# Demo1.net
KiCad netlist of a schematic drawn in Altium Designer
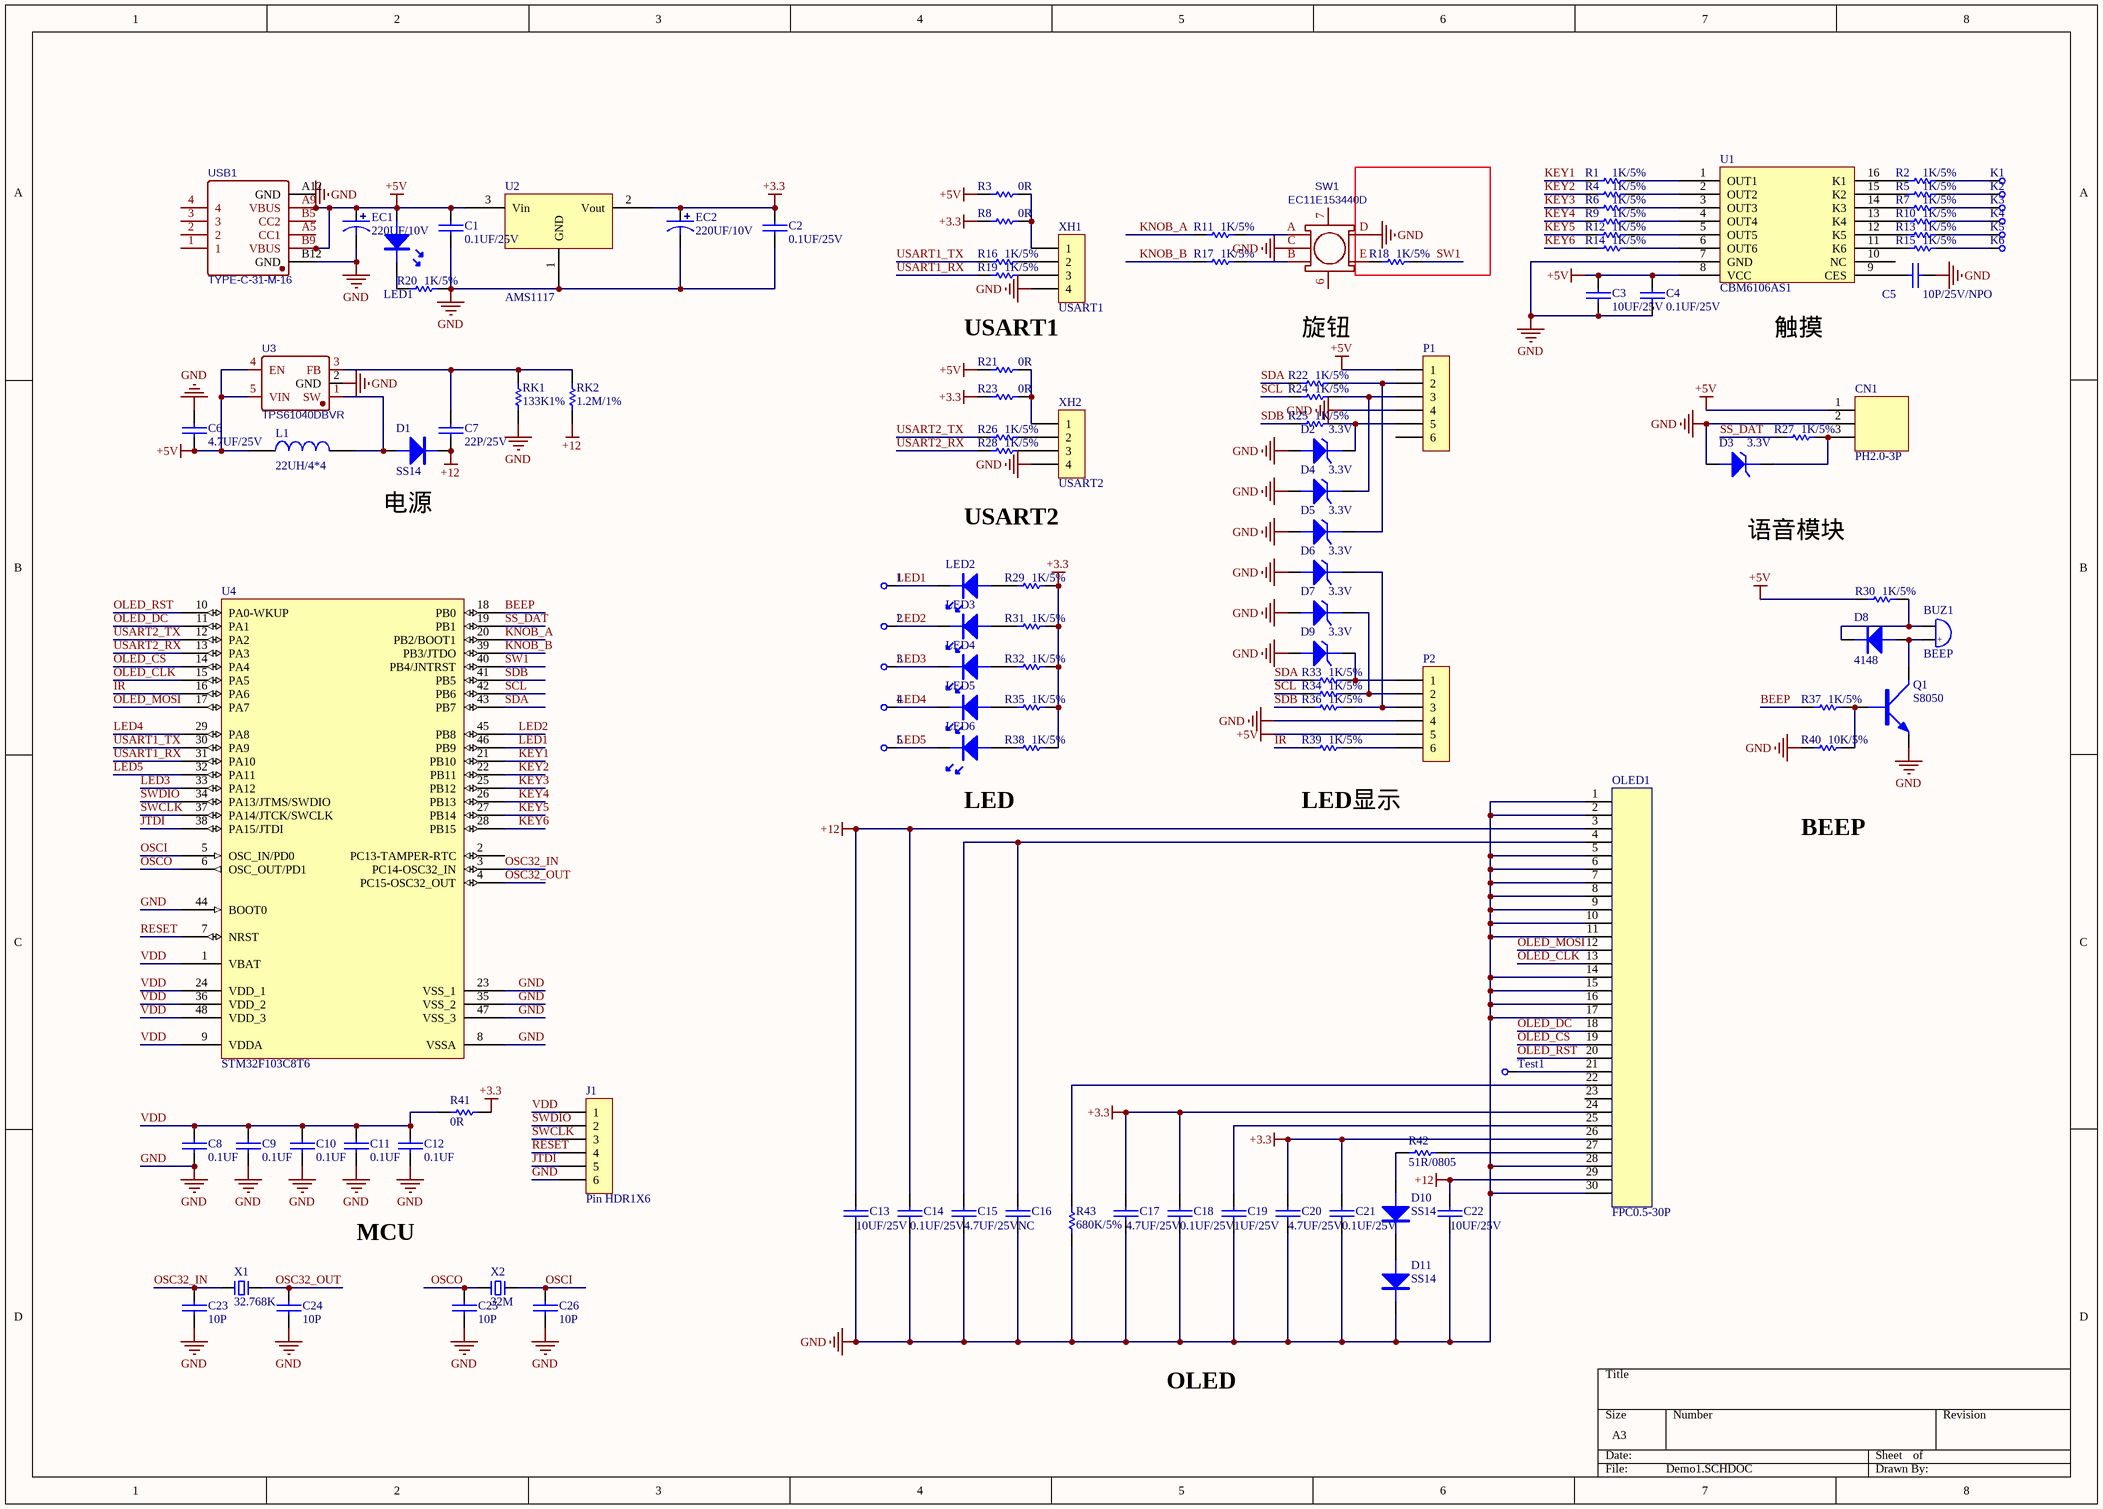
[diagram p0: Demo1.SCHDOC]

(export (version "E")
  (design (tool "Eeschema 10.0.6"))
  (components
    (comp (ref "1")
      (value "CHECK")
      (footprint "CHECK-A")
      (description "测试点")
      (libsource (lib "Fszhang") (part "CHECK"))
    )
    (comp (ref "2")
      (value "CHECK")
      (footprint "CHECK-A")
      (description "测试点")
      (libsource (lib "Fszhang") (part "CHECK"))
    )
    (comp (ref "3")
      (value "CHECK")
      (footprint "CHECK-A")
      (description "测试点")
      (libsource (lib "Fszhang") (part "CHECK"))
    )
    (comp (ref "4")
      (value "CHECK")
      (footprint "CHECK-A")
      (description "测试点")
      (libsource (lib "Fszhang") (part "CHECK"))
    )
    (comp (ref "5")
      (value "CHECK")
      (footprint "CHECK-A")
      (description "测试点")
      (libsource (lib "Fszhang") (part "CHECK"))
    )
    (comp (ref "BUZ1")
      (value "BEEP")
      (footprint "BEEP 6.5x12x6")
      (description "蜂鸣器")
      (libsource (lib "蜂鸣器") (part "BEEP"))
    )
    (comp (ref "C1")
      (value "0.1UF/25V")
      (footprint "0603C")
      (description "无极性电容")
      (libsource (lib "电容") (part "CAP"))
    )
    (comp (ref "C2")
      (value "0.1UF/25V")
      (footprint "0603C")
      (description "无极性电容")
      (libsource (lib "电容") (part "CAP"))
    )
    (comp (ref "C3")
      (value "10UF/25V")
      (footprint "0603C")
      (description "无极性电容")
      (libsource (lib "电容") (part "CAP"))
    )
    (comp (ref "C4")
      (value "0.1UF/25V")
      (footprint "0603C")
      (description "无极性电容")
      (libsource (lib "电容") (part "CAP"))
    )
    (comp (ref "C5")
      (value "10P/25V/NPO")
      (footprint "0603C")
      (description "无极性电容")
      (libsource (lib "电容") (part "CAP"))
    )
    (comp (ref "C6")
      (value "4.7UF/25V")
      (footprint "0603C")
      (description "无极性电容")
      (libsource (lib "电容") (part "CAP"))
    )
    (comp (ref "C7")
      (value "22P/25V")
      (footprint "0603C")
      (description "无极性电容")
      (libsource (lib "电容") (part "CAP"))
    )
    (comp (ref "C8")
      (value "0.1UF")
      (footprint "0603C")
      (description "无极性电容")
      (libsource (lib "电容") (part "CAP"))
    )
    (comp (ref "C9")
      (value "0.1UF")
      (footprint "0603C")
      (description "无极性电容")
      (libsource (lib "电容") (part "CAP"))
    )
    (comp (ref "C10")
      (value "0.1UF")
      (footprint "0603C")
      (description "无极性电容")
      (libsource (lib "电容") (part "CAP"))
    )
    (comp (ref "C11")
      (value "0.1UF")
      (footprint "0603C")
      (description "无极性电容")
      (libsource (lib "电容") (part "CAP"))
    )
    (comp (ref "C12")
      (value "0.1UF")
      (footprint "0603C")
      (description "无极性电容")
      (libsource (lib "电容") (part "CAP"))
    )
    (comp (ref "C13")
      (value "10UF/25V")
      (footprint "0603C")
      (description "无极性电容")
      (libsource (lib "电容") (part "CAP"))
    )
    (comp (ref "C14")
      (value "0.1UF/25V")
      (footprint "0603C")
      (description "无极性电容")
      (libsource (lib "电容") (part "CAP"))
    )
    (comp (ref "C15")
      (value "4.7UF/25V")
      (footprint "0603C")
      (description "无极性电容")
      (libsource (lib "电容") (part "CAP"))
    )
    (comp (ref "C16")
      (value "NC")
      (footprint "0603C")
      (description "无极性电容")
      (libsource (lib "电容") (part "CAP"))
    )
    (comp (ref "C17")
      (value "4.7UF/25V")
      (footprint "0603C")
      (description "无极性电容")
      (libsource (lib "电容") (part "CAP"))
    )
    (comp (ref "C18")
      (value "0.1UF/25V")
      (footprint "0603C")
      (description "无极性电容")
      (libsource (lib "电容") (part "CAP"))
    )
    (comp (ref "C19")
      (value "1UF/25V")
      (footprint "0603C")
      (description "无极性电容")
      (libsource (lib "电容") (part "CAP"))
    )
    (comp (ref "C20")
      (value "4.7UF/25V")
      (footprint "0603C")
      (description "无极性电容")
      (libsource (lib "电容") (part "CAP"))
    )
    (comp (ref "C21")
      (value "0.1UF/25V")
      (footprint "0603C")
      (description "无极性电容")
      (libsource (lib "电容") (part "CAP"))
    )
    (comp (ref "C22")
      (value "10UF/25V")
      (footprint "0603C")
      (description "无极性电容")
      (libsource (lib "电容") (part "CAP"))
    )
    (comp (ref "C23")
      (value "10P")
      (footprint "0603C")
      (description "无极性电容")
      (libsource (lib "电容") (part "CAP"))
    )
    (comp (ref "C24")
      (value "10P")
      (footprint "0603C")
      (description "无极性电容")
      (libsource (lib "电容") (part "CAP"))
    )
    (comp (ref "C25")
      (value "10P")
      (footprint "0603C")
      (description "无极性电容")
      (libsource (lib "电容") (part "CAP"))
    )
    (comp (ref "C26")
      (value "10P")
      (footprint "0603C")
      (description "无极性电容")
      (libsource (lib "电容") (part "CAP"))
    )
    (comp (ref "CN1") (value "PH2.0-3P") (footprint "PH2.0-3P") (libsource (lib "PH") (part "PH2.0-3P")))
    (comp (ref "D1")
      (value "SS14")
      (footprint "SMA/DO-214AC")
      (description "普通二极管")
      (libsource (lib "二极管") (part "DIODE"))
    )
    (comp (ref "D2")
      (value "3.3V")
      (footprint "SOD-123")
      (description "稳压二极管")
      (libsource (lib "二极管") (part "DIODE ZENER"))
    )
    (comp (ref "D3")
      (value "3.3V")
      (footprint "SOD-123")
      (description "稳压二极管")
      (libsource (lib "二极管") (part "DIODE ZENER"))
    )
    (comp (ref "D4")
      (value "3.3V")
      (footprint "SOD-123")
      (description "稳压二极管")
      (libsource (lib "二极管") (part "DIODE ZENER"))
    )
    (comp (ref "D5")
      (value "3.3V")
      (footprint "SOD-123")
      (description "稳压二极管")
      (libsource (lib "二极管") (part "DIODE ZENER"))
    )
    (comp (ref "D6")
      (value "3.3V")
      (footprint "SOD-123")
      (description "稳压二极管")
      (libsource (lib "二极管") (part "DIODE ZENER"))
    )
    (comp (ref "D7")
      (value "3.3V")
      (footprint "SOD-123")
      (description "稳压二极管")
      (libsource (lib "二极管") (part "DIODE ZENER"))
    )
    (comp (ref "D8")
      (value "4148")
      (footprint "SOD-123")
      (description "普通二极管")
      (libsource (lib "二极管") (part "DIODE"))
    )
    (comp (ref "D9")
      (value "3.3V")
      (footprint "SOD-123")
      (description "稳压二极管")
      (libsource (lib "二极管") (part "DIODE ZENER"))
    )
    (comp (ref "D10")
      (value "SS14")
      (footprint "SMA/DO-214AC")
      (description "普通二极管")
      (libsource (lib "二极管") (part "DIODE"))
    )
    (comp (ref "D11")
      (value "SS14")
      (footprint "SMA/DO-214AC")
      (description "普通二极管")
      (libsource (lib "二极管") (part "DIODE"))
    )
    (comp (ref "EC1")
      (value "220UF/10V")
      (footprint "SMD-EC6.3X6.3X10")
      (description "贴片电解电容")
      (libsource (lib "电容") (part "SMD_ECAP"))
    )
    (comp (ref "EC2")
      (value "220UF/10V")
      (footprint "SMD-EC6.3X6.3X10")
      (description "贴片电解电容")
      (libsource (lib "电容") (part "SMD_ECAP"))
    )
    (comp (ref "J1")
      (value "Pin HDR1X6")
      (footprint "Pin HDR1X6/2.54mm-S")
      (libsource (lib "排针") (part "Pin HDR1X6"))
    )
    (comp (ref "K1")
      (value "CHECK")
      (footprint "CHECK-A")
      (description "测试点")
      (libsource (lib "Fszhang") (part "CHECK"))
    )
    (comp (ref "K2")
      (value "CHECK")
      (footprint "CHECK-A")
      (description "测试点")
      (libsource (lib "Fszhang") (part "CHECK"))
    )
    (comp (ref "K3")
      (value "CHECK")
      (footprint "CHECK-A")
      (description "测试点")
      (libsource (lib "Fszhang") (part "CHECK"))
    )
    (comp (ref "K4")
      (value "CHECK")
      (footprint "CHECK-A")
      (description "测试点")
      (libsource (lib "Fszhang") (part "CHECK"))
    )
    (comp (ref "K5")
      (value "CHECK")
      (footprint "CHECK-A")
      (description "测试点")
      (libsource (lib "Fszhang") (part "CHECK"))
    )
    (comp (ref "K6")
      (value "CHECK")
      (footprint "CHECK-A")
      (description "测试点")
      (libsource (lib "Fszhang") (part "CHECK"))
    )
    (comp (ref "L1")
      (value "22UH/4*4")
      (footprint "CD42")
      (description "INDUCTOR")
      (libsource (lib "电感") (part "INDUCTOR"))
    )
    (comp (ref "LED1") (value "~") (footprint "LED-0603W") (libsource (lib "LED") (part "LED")))
    (comp (ref "LED2") (value "~") (footprint "LED-0603W") (libsource (lib "LED") (part "LED")))
    (comp (ref "LED3") (value "~") (footprint "LED-0603W") (libsource (lib "LED") (part "LED")))
    (comp (ref "LED4") (value "~") (footprint "LED-0603W") (libsource (lib "LED") (part "LED")))
    (comp (ref "LED5") (value "~") (footprint "LED-0603W") (libsource (lib "LED") (part "LED")))
    (comp (ref "LED6") (value "~") (footprint "LED-0603W") (libsource (lib "LED") (part "LED")))
    (comp (ref "OLED1")
      (value "FPC0.5-30P")
      (footprint "FPC0.5-30P")
      (description "贴片")
      (libsource (lib "FPC") (part "FPC0.5-30P"))
    )
    (comp (ref "P1") (value "~") (footprint "Pin HDR1X6/2.54mm-S") (libsource (lib "排针") (part "Pin HDR1X6")))
    (comp (ref "P2") (value "~") (footprint "Pin HDR1X6/2.54mm-S") (libsource (lib "排针") (part "Pin HDR1X6")))
    (comp (ref "Q1")
      (value "S8050")
      (footprint "SOT-23")
      (description "NPN三极管")
      (libsource (lib "三极管") (part "NPN"))
    )
    (comp (ref "R1") (value "1K/5%") (footprint "0603R") (libsource (lib "电阻") (part "RES")))
    (comp (ref "R2") (value "1K/5%") (footprint "0603R") (libsource (lib "电阻") (part "RES")))
    (comp (ref "R3") (value "0R") (footprint "0603R") (libsource (lib "电阻") (part "RES")))
    (comp (ref "R4") (value "1K/5%") (footprint "0603R") (libsource (lib "电阻") (part "RES")))
    (comp (ref "R5") (value "1K/5%") (footprint "0603R") (libsource (lib "电阻") (part "RES")))
    (comp (ref "R6") (value "1K/5%") (footprint "0603R") (libsource (lib "电阻") (part "RES")))
    (comp (ref "R7") (value "1K/5%") (footprint "0603R") (libsource (lib "电阻") (part "RES")))
    (comp (ref "R8") (value "0R") (footprint "0603R") (libsource (lib "电阻") (part "RES")))
    (comp (ref "R9") (value "1K/5%") (footprint "0603R") (libsource (lib "电阻") (part "RES")))
    (comp (ref "R10") (value "1K/5%") (footprint "0603R") (libsource (lib "电阻") (part "RES")))
    (comp (ref "R11") (value "1K/5%") (footprint "0603R") (libsource (lib "电阻") (part "RES")))
    (comp (ref "R12") (value "1K/5%") (footprint "0603R") (libsource (lib "电阻") (part "RES")))
    (comp (ref "R13") (value "1K/5%") (footprint "0603R") (libsource (lib "电阻") (part "RES")))
    (comp (ref "R14") (value "1K/5%") (footprint "0603R") (libsource (lib "电阻") (part "RES")))
    (comp (ref "R15") (value "1K/5%") (footprint "0603R") (libsource (lib "电阻") (part "RES")))
    (comp (ref "R16") (value "1K/5%") (footprint "0603R") (libsource (lib "电阻") (part "RES")))
    (comp (ref "R17") (value "1K/5%") (footprint "0603R") (libsource (lib "电阻") (part "RES")))
    (comp (ref "R18") (value "1K/5%") (footprint "0603R") (libsource (lib "电阻") (part "RES")))
    (comp (ref "R19") (value "1K/5%") (footprint "0603R") (libsource (lib "电阻") (part "RES")))
    (comp (ref "R20") (value "1K/5%") (footprint "0603R") (libsource (lib "电阻") (part "RES")))
    (comp (ref "R21") (value "0R") (footprint "0603R") (libsource (lib "电阻") (part "RES")))
    (comp (ref "R22") (value "1K/5%") (footprint "0603R") (libsource (lib "电阻") (part "RES")))
    (comp (ref "R23") (value "0R") (footprint "0603R") (libsource (lib "电阻") (part "RES")))
    (comp (ref "R24") (value "1K/5%") (footprint "0603R") (libsource (lib "电阻") (part "RES")))
    (comp (ref "R25") (value "1K/5%") (footprint "0603R") (libsource (lib "电阻") (part "RES")))
    (comp (ref "R26") (value "1K/5%") (footprint "0603R") (libsource (lib "电阻") (part "RES")))
    (comp (ref "R27") (value "1K/5%") (footprint "0603R") (libsource (lib "电阻") (part "RES")))
    (comp (ref "R28") (value "1K/5%") (footprint "0603R") (libsource (lib "电阻") (part "RES")))
    (comp (ref "R29") (value "1K/5%") (footprint "0603R") (libsource (lib "电阻") (part "RES")))
    (comp (ref "R30") (value "1K/5%") (footprint "0603R") (libsource (lib "电阻") (part "RES")))
    (comp (ref "R31") (value "1K/5%") (footprint "0603R") (libsource (lib "电阻") (part "RES")))
    (comp (ref "R32") (value "1K/5%") (footprint "0603R") (libsource (lib "电阻") (part "RES")))
    (comp (ref "R33") (value "1K/5%") (footprint "0603R") (libsource (lib "电阻") (part "RES")))
    (comp (ref "R34") (value "1K/5%") (footprint "0603R") (libsource (lib "电阻") (part "RES")))
    (comp (ref "R35") (value "1K/5%") (footprint "0603R") (libsource (lib "电阻") (part "RES")))
    (comp (ref "R36") (value "1K/5%") (footprint "0603R") (libsource (lib "电阻") (part "RES")))
    (comp (ref "R37") (value "1K/5%") (footprint "0603R") (libsource (lib "电阻") (part "RES")))
    (comp (ref "R38") (value "1K/5%") (footprint "0603R") (libsource (lib "电阻") (part "RES")))
    (comp (ref "R39") (value "1K/5%") (footprint "0603R") (libsource (lib "电阻") (part "RES")))
    (comp (ref "R40") (value "10K/5%") (footprint "0603R") (libsource (lib "电阻") (part "RES")))
    (comp (ref "R41") (value "0R") (footprint "0603R") (libsource (lib "电阻") (part "RES")))
    (comp (ref "R42") (value "51R/0805") (footprint "0805R") (libsource (lib "电阻") (part "RES")))
    (comp (ref "R43") (value "680K/5%") (footprint "0603R") (libsource (lib "电阻") (part "RES")))
    (comp (ref "RK1") (value "133K1%") (footprint "0603R") (libsource (lib "电阻") (part "RES")))
    (comp (ref "RK2") (value "1.2M/1%") (footprint "0603R") (libsource (lib "电阻") (part "RES")))
    (comp (ref "SW1")
      (value "EC11E153440D")
      (footprint "SW-TH_EC11XXXXXXXX")
      (fields (field (name "BOM_SUPPLIER PART") "C370992") (field (name "CONTRIBUTOR") "LCSC"))
      (libsource (lib "编码开关") (part "EC11E153440D"))
    )
    (comp (ref "Test1")
      (value "CHECK")
      (footprint "CHECK-A")
      (description "测试点")
      (libsource (lib "Fszhang") (part "CHECK"))
    )
    (comp (ref "U1")
      (value "CBM6106AS1")
      (footprint "SOP16")
      (libsource (lib "AD_SCH_LIB") (part "CBM6106AS1"))
    )
    (comp (ref "U2")
      (value "AMS1117")
      (footprint "SOT223")
      (description "三端稳压芯片")
      (libsource (lib "电源芯片") (part "AMS1117"))
    )
    (comp (ref "U3")
      (value "TPS61040DBVR")
      (footprint "SOT-23-5_L3.0-W1.7-P0.95-LS2.8-BR")
      (fields (field (name "BOM_SUPPLIER PART") "C7722"))
      (libsource (lib "Free Documents") (part "TPS61040DBVR"))
    )
    (comp (ref "U4")
      (value "STM32F103C8T6")
      (footprint "LQFP48 7X7")
      (libsource (lib "STM32系列") (part "STM32F103C8T6"))
    )
    (comp (ref "USB1")
      (value "TYPE-C-31-M-16")
      (footprint "TYPE-C-SMD_TYPE-C-31-M-16")
      (fields (field (name "BOM_SUPPLIER PART") "C283541") (field (name "CONTRIBUTOR") "LCSC"))
      (libsource (lib "USB") (part "TYPE-C-31-M-16"))
    )
    (comp (ref "X1")
      (value "32.768K")
      (footprint "OSC 3215-2P")
      (description "2脚无源脚晶振")
      (libsource (lib "晶振") (part "XTAL-2P"))
    )
    (comp (ref "X2")
      (value "32M")
      (footprint "OSC HC-49SMD")
      (description "2脚无源脚晶振")
      (libsource (lib "晶振") (part "XTAL-2P"))
    )
    (comp (ref "XH1") (value "USART1") (footprint "XH4/2.54mm/180") (libsource (lib "XH，VH") (part "XH4")))
    (comp (ref "XH2") (value "USART2") (footprint "XH4/2.54mm/180") (libsource (lib "XH，VH") (part "XH4")))
  )
  (nets
    (net (code "1") (name "+3.3") (class "Default")
      (node (ref "C17") (pin "2") (pinfunction "2_2") (pintype "passive"))
      (node (ref "C18") (pin "2") (pinfunction "2_2") (pintype "passive"))
      (node (ref "C2") (pin "2") (pinfunction "2_2") (pintype "passive"))
      (node (ref "C20") (pin "2") (pinfunction "2_2") (pintype "passive"))
      (node (ref "C21") (pin "2") (pinfunction "2_2") (pintype "passive"))
      (node (ref "EC2") (pin "1") (pinfunction "1_1") (pintype "passive"))
      (node (ref "OLED1") (pin "24") (pinfunction "24_24") (pintype "passive"))
      (node (ref "OLED1") (pin "26") (pinfunction "26_26") (pintype "passive"))
      (node (ref "R23") (pin "1") (pinfunction "1_1") (pintype "passive"))
      (node (ref "R29") (pin "1") (pinfunction "1_1") (pintype "passive"))
      (node (ref "R31") (pin "1") (pinfunction "1_1") (pintype "passive"))
      (node (ref "R32") (pin "1") (pinfunction "1_1") (pintype "passive"))
      (node (ref "R35") (pin "1") (pinfunction "1_1") (pintype "passive"))
      (node (ref "R38") (pin "1") (pinfunction "1_1") (pintype "passive"))
      (node (ref "R41") (pin "2") (pinfunction "2_2") (pintype "passive"))
      (node (ref "R8") (pin "1") (pinfunction "1_1") (pintype "passive"))
      (node (ref "U2") (pin "2") (pinfunction "Vout_2") (pintype "passive"))
    )
    (net (code "2") (name "+5V") (class "Default")
      (node (ref "C1") (pin "2") (pinfunction "2_2") (pintype "passive"))
      (node (ref "C3") (pin "2") (pinfunction "2_2") (pintype "passive"))
      (node (ref "C4") (pin "2") (pinfunction "2_2") (pintype "passive"))
      (node (ref "C6") (pin "1") (pinfunction "1_1") (pintype "passive"))
      (node (ref "CN1") (pin "1") (pinfunction "1_1") (pintype "passive"))
      (node (ref "EC1") (pin "1") (pinfunction "1_1") (pintype "passive"))
      (node (ref "L1") (pin "1") (pinfunction "1_1") (pintype "passive"))
      (node (ref "LED1") (pin "A") (pinfunction "A_A") (pintype "passive"))
      (node (ref "P1") (pin "1") (pinfunction "1_1") (pintype "passive"))
      (node (ref "P2") (pin "5") (pinfunction "5_5") (pintype "passive"))
      (node (ref "R21") (pin "1") (pinfunction "1_1") (pintype "passive"))
      (node (ref "R3") (pin "1") (pinfunction "1_1") (pintype "passive"))
      (node (ref "R30") (pin "2") (pinfunction "2_2") (pintype "passive"))
      (node (ref "U1") (pin "8") (pinfunction "VCC_8") (pintype "passive"))
      (node (ref "U2") (pin "3") (pinfunction "Vin_3") (pintype "passive"))
      (node (ref "U3") (pin "4") (pinfunction "EN_4") (pintype "passive"))
      (node (ref "U3") (pin "5") (pinfunction "VIN_5") (pintype "passive"))
      (node (ref "USB1") (pin "A9") (pinfunction "VBUS_A9") (pintype "passive"))
      (node (ref "USB1") (pin "B9") (pinfunction "VBUS_B9") (pintype "passive"))
    )
    (net (code "3") (name "+12") (class "Default")
      (node (ref "C13") (pin "2") (pinfunction "2_2") (pintype "passive"))
      (node (ref "C14") (pin "2") (pinfunction "2_2") (pintype "passive"))
      (node (ref "C22") (pin "2") (pinfunction "2_2") (pintype "passive"))
      (node (ref "C7") (pin "1") (pinfunction "1_1") (pintype "passive"))
      (node (ref "D1") (pin "K") (pinfunction "K_K") (pintype "passive"))
      (node (ref "OLED1") (pin "29") (pinfunction "29_29") (pintype "passive"))
      (node (ref "OLED1") (pin "3") (pinfunction "3_3") (pintype "passive"))
      (node (ref "RK2") (pin "1") (pinfunction "1_1") (pintype "passive"))
    )
    (net (code "4") (name "/BEEP") (class "Default")
      (node (ref "R37") (pin "2") (pinfunction "2_2") (pintype "passive"))
      (node (ref "U4") (pin "18") (pinfunction "PB0_18") (pintype "bidirectional"))
    )
    (net (code "5") (name "/IR") (class "Default")
      (node (ref "R39") (pin "2") (pinfunction "2_2") (pintype "passive"))
      (node (ref "U4") (pin "16") (pinfunction "PA6_16") (pintype "bidirectional"))
    )
    (net (code "6") (name "/JTDI") (class "Default")
      (node (ref "J1") (pin "5") (pinfunction "5_5") (pintype "passive"))
      (node (ref "U4") (pin "38") (pinfunction "PA15/JTDI_38") (pintype "bidirectional"))
    )
    (net (code "7") (name "/KEY1") (class "Default")
      (node (ref "R1") (pin "2") (pinfunction "2_2") (pintype "passive"))
      (node (ref "U4") (pin "21") (pinfunction "PB10_21") (pintype "bidirectional"))
    )
    (net (code "8") (name "/KEY2") (class "Default")
      (node (ref "R4") (pin "2") (pinfunction "2_2") (pintype "passive"))
      (node (ref "U4") (pin "22") (pinfunction "PB11_22") (pintype "bidirectional"))
    )
    (net (code "9") (name "/KEY3") (class "Default")
      (node (ref "R6") (pin "2") (pinfunction "2_2") (pintype "passive"))
      (node (ref "U4") (pin "25") (pinfunction "PB12_25") (pintype "bidirectional"))
    )
    (net (code "10") (name "/KEY4") (class "Default")
      (node (ref "R9") (pin "2") (pinfunction "2_2") (pintype "passive"))
      (node (ref "U4") (pin "26") (pinfunction "PB13_26") (pintype "bidirectional"))
    )
    (net (code "11") (name "/KEY5") (class "Default")
      (node (ref "R12") (pin "2") (pinfunction "2_2") (pintype "passive"))
      (node (ref "U4") (pin "27") (pinfunction "PB14_27") (pintype "bidirectional"))
    )
    (net (code "12") (name "/KEY6") (class "Default")
      (node (ref "R14") (pin "2") (pinfunction "2_2") (pintype "passive"))
      (node (ref "U4") (pin "28") (pinfunction "PB15_28") (pintype "bidirectional"))
    )
    (net (code "13") (name "/KNOB_A") (class "Default")
      (node (ref "R11") (pin "2") (pinfunction "2_2") (pintype "passive"))
      (node (ref "U4") (pin "20") (pinfunction "PB2/BOOT1_20") (pintype "bidirectional"))
    )
    (net (code "14") (name "/KNOB_B") (class "Default")
      (node (ref "R17") (pin "2") (pinfunction "2_2") (pintype "passive"))
      (node (ref "U4") (pin "39") (pinfunction "PB3/JTDO_39") (pintype "bidirectional"))
    )
    (net (code "15") (name "/LED1") (class "Default")
      (node (ref "1") (pin "1") (pinfunction "1_1") (pintype "passive"))
      (node (ref "LED2") (pin "K") (pinfunction "K_K") (pintype "passive"))
      (node (ref "U4") (pin "46") (pinfunction "PB9_46") (pintype "bidirectional"))
    )
    (net (code "16") (name "/LED2") (class "Default")
      (node (ref "2") (pin "1") (pinfunction "1_1") (pintype "passive"))
      (node (ref "LED3") (pin "K") (pinfunction "K_K") (pintype "passive"))
      (node (ref "U4") (pin "45") (pinfunction "PB8_45") (pintype "bidirectional"))
    )
    (net (code "17") (name "/LED3") (class "Default")
      (node (ref "3") (pin "1") (pinfunction "1_1") (pintype "passive"))
      (node (ref "LED4") (pin "K") (pinfunction "K_K") (pintype "passive"))
      (node (ref "U4") (pin "33") (pinfunction "PA12_33") (pintype "bidirectional"))
    )
    (net (code "18") (name "/LED4") (class "Default")
      (node (ref "4") (pin "1") (pinfunction "1_1") (pintype "passive"))
      (node (ref "LED5") (pin "K") (pinfunction "K_K") (pintype "passive"))
      (node (ref "U4") (pin "29") (pinfunction "PA8_29") (pintype "bidirectional"))
    )
    (net (code "19") (name "/LED5") (class "Default")
      (node (ref "5") (pin "1") (pinfunction "1_1") (pintype "passive"))
      (node (ref "LED6") (pin "K") (pinfunction "K_K") (pintype "passive"))
      (node (ref "U4") (pin "32") (pinfunction "PA11_32") (pintype "bidirectional"))
    )
    (net (code "20") (name "/OLED_CLK") (class "Default")
      (node (ref "OLED1") (pin "13") (pinfunction "13_13") (pintype "passive"))
      (node (ref "U4") (pin "15") (pinfunction "PA5_15") (pintype "bidirectional"))
    )
    (net (code "21") (name "/OLED_CS") (class "Default")
      (node (ref "OLED1") (pin "19") (pinfunction "19_19") (pintype "passive"))
      (node (ref "U4") (pin "14") (pinfunction "PA4_14") (pintype "bidirectional"))
    )
    (net (code "22") (name "/OLED_DC") (class "Default")
      (node (ref "OLED1") (pin "18") (pinfunction "18_18") (pintype "passive"))
      (node (ref "U4") (pin "11") (pinfunction "PA1_11") (pintype "bidirectional"))
    )
    (net (code "23") (name "/OLED_MOSI") (class "Default")
      (node (ref "OLED1") (pin "12") (pinfunction "12_12") (pintype "passive"))
      (node (ref "U4") (pin "17") (pinfunction "PA7_17") (pintype "bidirectional"))
    )
    (net (code "24") (name "/OLED_RST") (class "Default")
      (node (ref "OLED1") (pin "20") (pinfunction "20_20") (pintype "passive"))
      (node (ref "U4") (pin "10") (pinfunction "PA0-WKUP_10") (pintype "bidirectional"))
    )
    (net (code "25") (name "/OSC32_IN") (class "Default")
      (node (ref "C23") (pin "2") (pinfunction "2_2") (pintype "passive"))
      (node (ref "U4") (pin "3") (pinfunction "PC14-OSC32_IN_3") (pintype "bidirectional"))
      (node (ref "X1") (pin "1") (pinfunction "1_1") (pintype "passive"))
    )
    (net (code "26") (name "/OSC32_OUT") (class "Default")
      (node (ref "C24") (pin "2") (pinfunction "2_2") (pintype "passive"))
      (node (ref "U4") (pin "4") (pinfunction "PC15-OSC32_OUT_4") (pintype "bidirectional"))
      (node (ref "X1") (pin "2") (pinfunction "2_2") (pintype "passive"))
    )
    (net (code "27") (name "/OSCI") (class "Default")
      (node (ref "C26") (pin "2") (pinfunction "2_2") (pintype "passive"))
      (node (ref "U4") (pin "5") (pinfunction "OSC_IN/PD0_5") (pintype "input"))
      (node (ref "X2") (pin "2") (pinfunction "2_2") (pintype "passive"))
    )
    (net (code "28") (name "/OSCO") (class "Default")
      (node (ref "C25") (pin "2") (pinfunction "2_2") (pintype "passive"))
      (node (ref "U4") (pin "6") (pinfunction "OSC_OUT/PD1_6") (pintype "output"))
      (node (ref "X2") (pin "1") (pinfunction "1_1") (pintype "passive"))
    )
    (net (code "29") (name "/RESET") (class "Default")
      (node (ref "J1") (pin "4") (pinfunction "4_4") (pintype "passive"))
      (node (ref "U4") (pin "7") (pinfunction "NRST_7") (pintype "bidirectional"))
    )
    (net (code "30") (name "/SCL") (class "Default")
      (node (ref "R24") (pin "2") (pinfunction "2_2") (pintype "passive"))
      (node (ref "R34") (pin "2") (pinfunction "2_2") (pintype "passive"))
      (node (ref "U4") (pin "42") (pinfunction "PB6_42") (pintype "bidirectional"))
    )
    (net (code "31") (name "/SDA") (class "Default")
      (node (ref "R22") (pin "2") (pinfunction "2_2") (pintype "passive"))
      (node (ref "R33") (pin "2") (pinfunction "2_2") (pintype "passive"))
      (node (ref "U4") (pin "43") (pinfunction "PB7_43") (pintype "bidirectional"))
    )
    (net (code "32") (name "/SDB") (class "Default")
      (node (ref "R25") (pin "2") (pinfunction "2_2") (pintype "passive"))
      (node (ref "R36") (pin "2") (pinfunction "2_2") (pintype "passive"))
      (node (ref "U4") (pin "41") (pinfunction "PB5_41") (pintype "bidirectional"))
    )
    (net (code "33") (name "/SS_DAT") (class "Default")
      (node (ref "R27") (pin "2") (pinfunction "2_2") (pintype "passive"))
      (node (ref "U4") (pin "19") (pinfunction "PB1_19") (pintype "bidirectional"))
    )
    (net (code "34") (name "/SW1") (class "Default")
      (node (ref "R18") (pin "1") (pinfunction "1_1") (pintype "passive"))
      (node (ref "U4") (pin "40") (pinfunction "PB4/JNTRST_40") (pintype "bidirectional"))
    )
    (net (code "35") (name "/SWCLK") (class "Default")
      (node (ref "J1") (pin "3") (pinfunction "3_3") (pintype "passive"))
      (node (ref "U4") (pin "37") (pinfunction "PA14/JTCK/SWCLK_37") (pintype "bidirectional"))
    )
    (net (code "36") (name "/SWDIO") (class "Default")
      (node (ref "J1") (pin "2") (pinfunction "2_2") (pintype "passive"))
      (node (ref "U4") (pin "34") (pinfunction "PA13/JTMS/SWDIO_34") (pintype "bidirectional"))
    )
    (net (code "37") (name "/USART1_RX") (class "Default")
      (node (ref "R19") (pin "2") (pinfunction "2_2") (pintype "passive"))
      (node (ref "U4") (pin "31") (pinfunction "PA10_31") (pintype "bidirectional"))
    )
    (net (code "38") (name "/USART1_TX") (class "Default")
      (node (ref "R16") (pin "2") (pinfunction "2_2") (pintype "passive"))
      (node (ref "U4") (pin "30") (pinfunction "PA9_30") (pintype "bidirectional"))
    )
    (net (code "39") (name "/USART2_RX") (class "Default")
      (node (ref "R28") (pin "2") (pinfunction "2_2") (pintype "passive"))
      (node (ref "U4") (pin "13") (pinfunction "PA3_13") (pintype "bidirectional"))
    )
    (net (code "40") (name "/USART2_TX") (class "Default")
      (node (ref "R26") (pin "2") (pinfunction "2_2") (pintype "passive"))
      (node (ref "U4") (pin "12") (pinfunction "PA2_12") (pintype "bidirectional"))
    )
    (net (code "41") (name "/VDD") (class "Default")
      (node (ref "C10") (pin "2") (pinfunction "2_2") (pintype "passive"))
      (node (ref "C11") (pin "2") (pinfunction "2_2") (pintype "passive"))
      (node (ref "C12") (pin "2") (pinfunction "2_2") (pintype "passive"))
      (node (ref "C8") (pin "2") (pinfunction "2_2") (pintype "passive"))
      (node (ref "C9") (pin "2") (pinfunction "2_2") (pintype "passive"))
      (node (ref "J1") (pin "1") (pinfunction "1_1") (pintype "passive"))
      (node (ref "R41") (pin "1") (pinfunction "1_1") (pintype "passive"))
      (node (ref "U4") (pin "1") (pinfunction "VBAT_1") (pintype "power_in"))
      (node (ref "U4") (pin "24") (pinfunction "VDD_1_24") (pintype "power_in"))
      (node (ref "U4") (pin "36") (pinfunction "VDD_2_36") (pintype "power_in"))
      (node (ref "U4") (pin "48") (pinfunction "VDD_3_48") (pintype "power_in"))
      (node (ref "U4") (pin "9") (pinfunction "VDDA_9") (pintype "power_in"))
    )
    (net (code "42") (name "GND") (class "Default")
      (node (ref "C1") (pin "1") (pinfunction "1_1") (pintype "passive"))
      (node (ref "C10") (pin "1") (pinfunction "1_1") (pintype "passive"))
      (node (ref "C11") (pin "1") (pinfunction "1_1") (pintype "passive"))
      (node (ref "C12") (pin "1") (pinfunction "1_1") (pintype "passive"))
      (node (ref "C13") (pin "1") (pinfunction "1_1") (pintype "passive"))
      (node (ref "C14") (pin "1") (pinfunction "1_1") (pintype "passive"))
      (node (ref "C15") (pin "1") (pinfunction "1_1") (pintype "passive"))
      (node (ref "C16") (pin "1") (pinfunction "1_1") (pintype "passive"))
      (node (ref "C17") (pin "1") (pinfunction "1_1") (pintype "passive"))
      (node (ref "C18") (pin "1") (pinfunction "1_1") (pintype "passive"))
      (node (ref "C19") (pin "1") (pinfunction "1_1") (pintype "passive"))
      (node (ref "C2") (pin "1") (pinfunction "1_1") (pintype "passive"))
      (node (ref "C20") (pin "1") (pinfunction "1_1") (pintype "passive"))
      (node (ref "C21") (pin "1") (pinfunction "1_1") (pintype "passive"))
      (node (ref "C22") (pin "1") (pinfunction "1_1") (pintype "passive"))
      (node (ref "C23") (pin "1") (pinfunction "1_1") (pintype "passive"))
      (node (ref "C24") (pin "1") (pinfunction "1_1") (pintype "passive"))
      (node (ref "C25") (pin "1") (pinfunction "1_1") (pintype "passive"))
      (node (ref "C26") (pin "1") (pinfunction "1_1") (pintype "passive"))
      (node (ref "C3") (pin "1") (pinfunction "1_1") (pintype "passive"))
      (node (ref "C4") (pin "1") (pinfunction "1_1") (pintype "passive"))
      (node (ref "C5") (pin "1") (pinfunction "1_1") (pintype "passive"))
      (node (ref "C6") (pin "2") (pinfunction "2_2") (pintype "passive"))
      (node (ref "C8") (pin "1") (pinfunction "1_1") (pintype "passive"))
      (node (ref "C9") (pin "1") (pinfunction "1_1") (pintype "passive"))
      (node (ref "CN1") (pin "2") (pinfunction "2_2") (pintype "passive"))
      (node (ref "D11") (pin "K") (pinfunction "K_K") (pintype "passive"))
      (node (ref "D2") (pin "A") (pinfunction "A_A") (pintype "passive"))
      (node (ref "D3") (pin "A") (pinfunction "A_A") (pintype "passive"))
      (node (ref "D4") (pin "A") (pinfunction "A_A") (pintype "passive"))
      (node (ref "D5") (pin "A") (pinfunction "A_A") (pintype "passive"))
      (node (ref "D6") (pin "A") (pinfunction "A_A") (pintype "passive"))
      (node (ref "D7") (pin "A") (pinfunction "A_A") (pintype "passive"))
      (node (ref "D9") (pin "A") (pinfunction "A_A") (pintype "passive"))
      (node (ref "EC1") (pin "2") (pinfunction "2_2") (pintype "passive"))
      (node (ref "EC2") (pin "2") (pinfunction "2_2") (pintype "passive"))
      (node (ref "J1") (pin "6") (pinfunction "6_6") (pintype "passive"))
      (node (ref "OLED1") (pin "1") (pinfunction "1_1") (pintype "passive"))
      (node (ref "OLED1") (pin "10") (pinfunction "10_10") (pintype "passive"))
      (node (ref "OLED1") (pin "11") (pinfunction "11_11") (pintype "passive"))
      (node (ref "OLED1") (pin "14") (pinfunction "14_14") (pintype "passive"))
      (node (ref "OLED1") (pin "15") (pinfunction "15_15") (pintype "passive"))
      (node (ref "OLED1") (pin "16") (pinfunction "16_16") (pintype "passive"))
      (node (ref "OLED1") (pin "17") (pinfunction "17_17") (pintype "passive"))
      (node (ref "OLED1") (pin "2") (pinfunction "2_2") (pintype "passive"))
      (node (ref "OLED1") (pin "28") (pinfunction "28_28") (pintype "passive"))
      (node (ref "OLED1") (pin "30") (pinfunction "30_30") (pintype "passive"))
      (node (ref "OLED1") (pin "5") (pinfunction "5_5") (pintype "passive"))
      (node (ref "OLED1") (pin "6") (pinfunction "6_6") (pintype "passive"))
      (node (ref "OLED1") (pin "7") (pinfunction "7_7") (pintype "passive"))
      (node (ref "OLED1") (pin "8") (pinfunction "8_8") (pintype "passive"))
      (node (ref "OLED1") (pin "9") (pinfunction "9_9") (pintype "passive"))
      (node (ref "P1") (pin "4") (pinfunction "4_4") (pintype "passive"))
      (node (ref "P2") (pin "4") (pinfunction "4_4") (pintype "passive"))
      (node (ref "Q1") (pin "E") (pinfunction "E_E") (pintype "passive"))
      (node (ref "R20") (pin "1") (pinfunction "1_1") (pintype "passive"))
      (node (ref "R40") (pin "2") (pinfunction "2_2") (pintype "passive"))
      (node (ref "R43") (pin "1") (pinfunction "1_1") (pintype "passive"))
      (node (ref "RK1") (pin "1") (pinfunction "1_1") (pintype "passive"))
      (node (ref "SW1") (pin "C") (pinfunction "C_C") (pintype "passive"))
      (node (ref "SW1") (pin "D") (pinfunction "D_D") (pintype "passive"))
      (node (ref "U1") (pin "7") (pinfunction "GND_7") (pintype "passive"))
      (node (ref "U2") (pin "1") (pinfunction "GND_1") (pintype "passive"))
      (node (ref "U3") (pin "2") (pinfunction "GND_2") (pintype "passive"))
      (node (ref "U4") (pin "23") (pinfunction "VSS_1_23") (pintype "power_in"))
      (node (ref "U4") (pin "35") (pinfunction "VSS_2_35") (pintype "power_in"))
      (node (ref "U4") (pin "44") (pinfunction "BOOT0_44") (pintype "input"))
      (node (ref "U4") (pin "47") (pinfunction "VSS_3_47") (pintype "power_in"))
      (node (ref "U4") (pin "8") (pinfunction "VSSA_8") (pintype "power_in"))
      (node (ref "USB1") (pin "B12") (pinfunction "GND_B12") (pintype "passive"))
      (node (ref "XH1") (pin "4") (pinfunction "4_4") (pintype "passive"))
      (node (ref "XH2") (pin "4") (pinfunction "4_4") (pintype "passive"))
    )
    (net (code "43") (name "Net-(BUZ1-Pad1)") (class "Default")
      (node (ref "BUZ1") (pin "1") (pinfunction "1_1") (pintype "passive"))
      (node (ref "D8") (pin "A") (pinfunction "A_A") (pintype "passive"))
      (node (ref "Q1") (pin "C") (pinfunction "C_C") (pintype "passive"))
    )
    (net (code "44") (name "Net-(BUZ1-Pad2)") (class "Default")
      (node (ref "BUZ1") (pin "2") (pinfunction "2_2") (pintype "passive"))
      (node (ref "D8") (pin "K") (pinfunction "K_K") (pintype "passive"))
      (node (ref "R30") (pin "1") (pinfunction "1_1") (pintype "passive"))
    )
    (net (code "45") (name "Net-(C15-Pad2)") (class "Default")
      (node (ref "C15") (pin "2") (pinfunction "2_2") (pintype "passive"))
      (node (ref "C16") (pin "2") (pinfunction "2_2") (pintype "passive"))
      (node (ref "OLED1") (pin "4") (pinfunction "4_4") (pintype "passive"))
    )
    (net (code "46") (name "Net-(C19-Pad2)") (class "Default")
      (node (ref "C19") (pin "2") (pinfunction "2_2") (pintype "passive"))
      (node (ref "OLED1") (pin "25") (pinfunction "25_25") (pintype "passive"))
    )
    (net (code "47") (name "Net-(CN1-Pad3)") (class "Default")
      (node (ref "CN1") (pin "3") (pinfunction "3_3") (pintype "passive"))
      (node (ref "D3") (pin "K") (pinfunction "K_K") (pintype "passive"))
      (node (ref "R27") (pin "1") (pinfunction "1_1") (pintype "passive"))
    )
    (net (code "48") (name "Net-(D2-PadK)") (class "Default")
      (node (ref "D2") (pin "K") (pinfunction "K_K") (pintype "passive"))
      (node (ref "P1") (pin "5") (pinfunction "5_5") (pintype "passive"))
      (node (ref "R25") (pin "1") (pinfunction "1_1") (pintype "passive"))
    )
    (net (code "49") (name "Net-(D4-PadK)") (class "Default")
      (node (ref "D4") (pin "K") (pinfunction "K_K") (pintype "passive"))
      (node (ref "P1") (pin "3") (pinfunction "3_3") (pintype "passive"))
      (node (ref "R24") (pin "1") (pinfunction "1_1") (pintype "passive"))
    )
    (net (code "50") (name "Net-(D5-PadK)") (class "Default")
      (node (ref "D5") (pin "K") (pinfunction "K_K") (pintype "passive"))
      (node (ref "P1") (pin "2") (pinfunction "2_2") (pintype "passive"))
      (node (ref "R22") (pin "1") (pinfunction "1_1") (pintype "passive"))
    )
    (net (code "51") (name "Net-(D6-PadK)") (class "Default")
      (node (ref "D6") (pin "K") (pinfunction "K_K") (pintype "passive"))
      (node (ref "P2") (pin "3") (pinfunction "3_3") (pintype "passive"))
      (node (ref "R36") (pin "1") (pinfunction "1_1") (pintype "passive"))
    )
    (net (code "52") (name "Net-(D7-PadK)") (class "Default")
      (node (ref "D7") (pin "K") (pinfunction "K_K") (pintype "passive"))
      (node (ref "P2") (pin "2") (pinfunction "2_2") (pintype "passive"))
      (node (ref "R34") (pin "1") (pinfunction "1_1") (pintype "passive"))
    )
    (net (code "53") (name "Net-(D9-PadK)") (class "Default")
      (node (ref "D9") (pin "K") (pinfunction "K_K") (pintype "passive"))
      (node (ref "P2") (pin "1") (pinfunction "1_1") (pintype "passive"))
      (node (ref "R33") (pin "1") (pinfunction "1_1") (pintype "passive"))
    )
    (net (code "54") (name "Net-(D10-PadA)") (class "Default")
      (node (ref "D10") (pin "A") (pinfunction "A_A") (pintype "passive"))
      (node (ref "R42") (pin "1") (pinfunction "1_1") (pintype "passive"))
    )
    (net (code "55") (name "Net-(D10-PadK)") (class "Default")
      (node (ref "D10") (pin "K") (pinfunction "K_K") (pintype "passive"))
      (node (ref "D11") (pin "A") (pinfunction "A_A") (pintype "passive"))
    )
    (net (code "56") (name "Net-(K1-Pad1)") (class "Default")
      (node (ref "K1") (pin "1") (pinfunction "1_1") (pintype "passive"))
      (node (ref "R2") (pin "1") (pinfunction "1_1") (pintype "passive"))
    )
    (net (code "57") (name "Net-(K2-Pad1)") (class "Default")
      (node (ref "K2") (pin "1") (pinfunction "1_1") (pintype "passive"))
      (node (ref "R5") (pin "1") (pinfunction "1_1") (pintype "passive"))
    )
    (net (code "58") (name "Net-(K3-Pad1)") (class "Default")
      (node (ref "K3") (pin "1") (pinfunction "1_1") (pintype "passive"))
      (node (ref "R7") (pin "1") (pinfunction "1_1") (pintype "passive"))
    )
    (net (code "59") (name "Net-(K4-Pad1)") (class "Default")
      (node (ref "K4") (pin "1") (pinfunction "1_1") (pintype "passive"))
      (node (ref "R10") (pin "1") (pinfunction "1_1") (pintype "passive"))
    )
    (net (code "60") (name "Net-(K5-Pad1)") (class "Default")
      (node (ref "K5") (pin "1") (pinfunction "1_1") (pintype "passive"))
      (node (ref "R13") (pin "1") (pinfunction "1_1") (pintype "passive"))
    )
    (net (code "61") (name "Net-(K6-Pad1)") (class "Default")
      (node (ref "K6") (pin "1") (pinfunction "1_1") (pintype "passive"))
      (node (ref "R15") (pin "1") (pinfunction "1_1") (pintype "passive"))
    )
    (net (code "62") (name "Net-(LED1-PadK)") (class "Default")
      (node (ref "LED1") (pin "K") (pinfunction "K_K") (pintype "passive"))
      (node (ref "R20") (pin "2") (pinfunction "2_2") (pintype "passive"))
    )
    (net (code "63") (name "Net-(LED2-PadA)") (class "Default")
      (node (ref "LED2") (pin "A") (pinfunction "A_A") (pintype "passive"))
      (node (ref "R29") (pin "2") (pinfunction "2_2") (pintype "passive"))
    )
    (net (code "64") (name "Net-(LED3-PadA)") (class "Default")
      (node (ref "LED3") (pin "A") (pinfunction "A_A") (pintype "passive"))
      (node (ref "R31") (pin "2") (pinfunction "2_2") (pintype "passive"))
    )
    (net (code "65") (name "Net-(LED4-PadA)") (class "Default")
      (node (ref "LED4") (pin "A") (pinfunction "A_A") (pintype "passive"))
      (node (ref "R32") (pin "2") (pinfunction "2_2") (pintype "passive"))
    )
    (net (code "66") (name "Net-(LED5-PadA)") (class "Default")
      (node (ref "LED5") (pin "A") (pinfunction "A_A") (pintype "passive"))
      (node (ref "R35") (pin "2") (pinfunction "2_2") (pintype "passive"))
    )
    (net (code "67") (name "Net-(LED6-PadA)") (class "Default")
      (node (ref "LED6") (pin "A") (pinfunction "A_A") (pintype "passive"))
      (node (ref "R38") (pin "2") (pinfunction "2_2") (pintype "passive"))
    )
    (net (code "68") (name "Net-(OLED1-Pad21)") (class "Default")
      (node (ref "OLED1") (pin "21") (pinfunction "21_21") (pintype "passive"))
      (node (ref "Test1") (pin "1") (pinfunction "1_1") (pintype "passive"))
    )
    (net (code "69") (name "Net-(OLED1-Pad22)") (class "Default")
      (node (ref "OLED1") (pin "22") (pinfunction "22_22") (pintype "passive"))
      (node (ref "R43") (pin "2") (pinfunction "2_2") (pintype "passive"))
    )
    (net (code "70") (name "Net-(OLED1-Pad27)") (class "Default")
      (node (ref "OLED1") (pin "27") (pinfunction "27_27") (pintype "passive"))
      (node (ref "R42") (pin "2") (pinfunction "2_2") (pintype "passive"))
    )
    (net (code "71") (name "Net-(P2-Pad6)") (class "Default")
      (node (ref "P2") (pin "6") (pinfunction "6_6") (pintype "passive"))
      (node (ref "R39") (pin "1") (pinfunction "1_1") (pintype "passive"))
    )
    (net (code "72") (name "Net-(Q1-PadB)") (class "Default")
      (node (ref "Q1") (pin "B") (pinfunction "B_B") (pintype "passive"))
      (node (ref "R37") (pin "1") (pinfunction "1_1") (pintype "passive"))
      (node (ref "R40") (pin "1") (pinfunction "1_1") (pintype "passive"))
    )
    (net (code "73") (name "Net-(R3-Pad2)") (class "Default")
      (node (ref "R3") (pin "2") (pinfunction "2_2") (pintype "passive"))
      (node (ref "R8") (pin "2") (pinfunction "2_2") (pintype "passive"))
      (node (ref "XH1") (pin "1") (pinfunction "1_1") (pintype "passive"))
    )
    (net (code "74") (name "Net-(R11-Pad1)") (class "Default")
      (node (ref "R11") (pin "1") (pinfunction "1_1") (pintype "passive"))
      (node (ref "SW1") (pin "A") (pinfunction "A_A") (pintype "passive"))
    )
    (net (code "75") (name "Net-(R16-Pad1)") (class "Default")
      (node (ref "R16") (pin "1") (pinfunction "1_1") (pintype "passive"))
      (node (ref "XH1") (pin "2") (pinfunction "2_2") (pintype "passive"))
    )
    (net (code "76") (name "Net-(R17-Pad1)") (class "Default")
      (node (ref "R17") (pin "1") (pinfunction "1_1") (pintype "passive"))
      (node (ref "SW1") (pin "B") (pinfunction "B_B") (pintype "passive"))
    )
    (net (code "77") (name "Net-(R18-Pad2)") (class "Default")
      (node (ref "R18") (pin "2") (pinfunction "2_2") (pintype "passive"))
      (node (ref "SW1") (pin "E") (pinfunction "E_E") (pintype "passive"))
    )
    (net (code "78") (name "Net-(R19-Pad1)") (class "Default")
      (node (ref "R19") (pin "1") (pinfunction "1_1") (pintype "passive"))
      (node (ref "XH1") (pin "3") (pinfunction "3_3") (pintype "passive"))
    )
    (net (code "79") (name "Net-(R21-Pad2)") (class "Default")
      (node (ref "R21") (pin "2") (pinfunction "2_2") (pintype "passive"))
      (node (ref "R23") (pin "2") (pinfunction "2_2") (pintype "passive"))
      (node (ref "XH2") (pin "1") (pinfunction "1_1") (pintype "passive"))
    )
    (net (code "80") (name "Net-(R26-Pad1)") (class "Default")
      (node (ref "R26") (pin "1") (pinfunction "1_1") (pintype "passive"))
      (node (ref "XH2") (pin "2") (pinfunction "2_2") (pintype "passive"))
    )
    (net (code "81") (name "Net-(R28-Pad1)") (class "Default")
      (node (ref "R28") (pin "1") (pinfunction "1_1") (pintype "passive"))
      (node (ref "XH2") (pin "3") (pinfunction "3_3") (pintype "passive"))
    )
    (net (code "82") (name "Net-(U1-CES)") (class "Default")
      (node (ref "C5") (pin "2") (pinfunction "2_2") (pintype "passive"))
      (node (ref "U1") (pin "9") (pinfunction "CES_9") (pintype "passive"))
    )
    (net (code "83") (name "Net-(U1-K1)") (class "Default")
      (node (ref "R2") (pin "2") (pinfunction "2_2") (pintype "passive"))
      (node (ref "U1") (pin "16") (pinfunction "K1_16") (pintype "passive"))
    )
    (net (code "84") (name "Net-(U1-K2)") (class "Default")
      (node (ref "R5") (pin "2") (pinfunction "2_2") (pintype "passive"))
      (node (ref "U1") (pin "15") (pinfunction "K2_15") (pintype "passive"))
    )
    (net (code "85") (name "Net-(U1-K3)") (class "Default")
      (node (ref "R7") (pin "2") (pinfunction "2_2") (pintype "passive"))
      (node (ref "U1") (pin "14") (pinfunction "K3_14") (pintype "passive"))
    )
    (net (code "86") (name "Net-(U1-K4)") (class "Default")
      (node (ref "R10") (pin "2") (pinfunction "2_2") (pintype "passive"))
      (node (ref "U1") (pin "13") (pinfunction "K4_13") (pintype "passive"))
    )
    (net (code "87") (name "Net-(U1-K5)") (class "Default")
      (node (ref "R13") (pin "2") (pinfunction "2_2") (pintype "passive"))
      (node (ref "U1") (pin "12") (pinfunction "K5_12") (pintype "passive"))
    )
    (net (code "88") (name "Net-(U1-K6)") (class "Default")
      (node (ref "R15") (pin "2") (pinfunction "2_2") (pintype "passive"))
      (node (ref "U1") (pin "11") (pinfunction "K6_11") (pintype "passive"))
    )
    (net (code "89") (name "Net-(U1-OUT1)") (class "Default")
      (node (ref "R1") (pin "1") (pinfunction "1_1") (pintype "passive"))
      (node (ref "U1") (pin "1") (pinfunction "OUT1_1") (pintype "passive"))
    )
    (net (code "90") (name "Net-(U1-OUT2)") (class "Default")
      (node (ref "R4") (pin "1") (pinfunction "1_1") (pintype "passive"))
      (node (ref "U1") (pin "2") (pinfunction "OUT2_2") (pintype "passive"))
    )
    (net (code "91") (name "Net-(U1-OUT3)") (class "Default")
      (node (ref "R6") (pin "1") (pinfunction "1_1") (pintype "passive"))
      (node (ref "U1") (pin "3") (pinfunction "OUT3_3") (pintype "passive"))
    )
    (net (code "92") (name "Net-(U1-OUT4)") (class "Default")
      (node (ref "R9") (pin "1") (pinfunction "1_1") (pintype "passive"))
      (node (ref "U1") (pin "4") (pinfunction "OUT4_4") (pintype "passive"))
    )
    (net (code "93") (name "Net-(U1-OUT5)") (class "Default")
      (node (ref "R12") (pin "1") (pinfunction "1_1") (pintype "passive"))
      (node (ref "U1") (pin "5") (pinfunction "OUT5_5") (pintype "passive"))
    )
    (net (code "94") (name "Net-(U1-OUT6)") (class "Default")
      (node (ref "R14") (pin "1") (pinfunction "1_1") (pintype "passive"))
      (node (ref "U1") (pin "6") (pinfunction "OUT6_6") (pintype "passive"))
    )
    (net (code "95") (name "Net-(U3-FB)") (class "Default")
      (node (ref "C7") (pin "2") (pinfunction "2_2") (pintype "passive"))
      (node (ref "RK1") (pin "2") (pinfunction "2_2") (pintype "passive"))
      (node (ref "RK2") (pin "2") (pinfunction "2_2") (pintype "passive"))
      (node (ref "U3") (pin "3") (pinfunction "FB_3") (pintype "passive"))
    )
    (net (code "96") (name "Net-(U3-SW)") (class "Default")
      (node (ref "D1") (pin "A") (pinfunction "A_A") (pintype "passive"))
      (node (ref "L1") (pin "2") (pinfunction "2_2") (pintype "passive"))
      (node (ref "U3") (pin "1") (pinfunction "SW_1") (pintype "passive"))
    )
    (net (code "97") (name "unconnected-(OLED1-Pad23)") (class "Default")
      (node (ref "OLED1") (pin "23") (pinfunction "23_23") (pintype "passive"))
    )
    (net (code "98") (name "unconnected-(P1-Pad6)") (class "Default")
      (node (ref "P1") (pin "6") (pinfunction "6_6") (pintype "passive"))
    )
    (net (code "99") (name "unconnected-(SW1-Pad6)") (class "Default")
      (node (ref "SW1") (pin "6") (pinfunction "6_6") (pintype "passive"))
    )
    (net (code "100") (name "unconnected-(SW1-Pad7)") (class "Default")
      (node (ref "SW1") (pin "7") (pinfunction "7_7") (pintype "passive"))
    )
    (net (code "101") (name "unconnected-(U1-NC-Pad10)") (class "Default")
      (node (ref "U1") (pin "10") (pinfunction "NC_10") (pintype "passive"))
    )
    (net (code "102") (name "unconnected-(U4-PC13-TAMPER-RTC-Pad2)") (class "Default")
      (node (ref "U4") (pin "2") (pinfunction "PC13-TAMPER-RTC_2") (pintype "bidirectional"))
    )
    (net (code "103") (name "unconnected-(USB1-CC1-PadA5)") (class "Default")
      (node (ref "USB1") (pin "A5") (pinfunction "CC1_A5") (pintype "passive"))
    )
    (net (code "104") (name "unconnected-(USB1-CC2-PadB5)") (class "Default")
      (node (ref "USB1") (pin "B5") (pinfunction "CC2_B5") (pintype "passive"))
    )
    (net (code "105") (name "unconnected-(USB1-GND-PadA12)") (class "Default")
      (node (ref "USB1") (pin "A12") (pinfunction "GND_A12") (pintype "passive"))
    )
    (net (code "106") (name "unconnected-(USB1-Pad1)") (class "Default")
      (node (ref "USB1") (pin "1") (pinfunction "1_1") (pintype "passive"))
    )
    (net (code "107") (name "unconnected-(USB1-Pad2)") (class "Default")
      (node (ref "USB1") (pin "2") (pinfunction "2_2") (pintype "passive"))
    )
    (net (code "108") (name "unconnected-(USB1-Pad3)") (class "Default")
      (node (ref "USB1") (pin "3") (pinfunction "3_3") (pintype "passive"))
    )
    (net (code "109") (name "unconnected-(USB1-Pad4)") (class "Default")
      (node (ref "USB1") (pin "4") (pinfunction "4_4") (pintype "passive"))
    )
  )
)
